# Schematic.net
KiCad netlist of a schematic drawn in Altium Designer
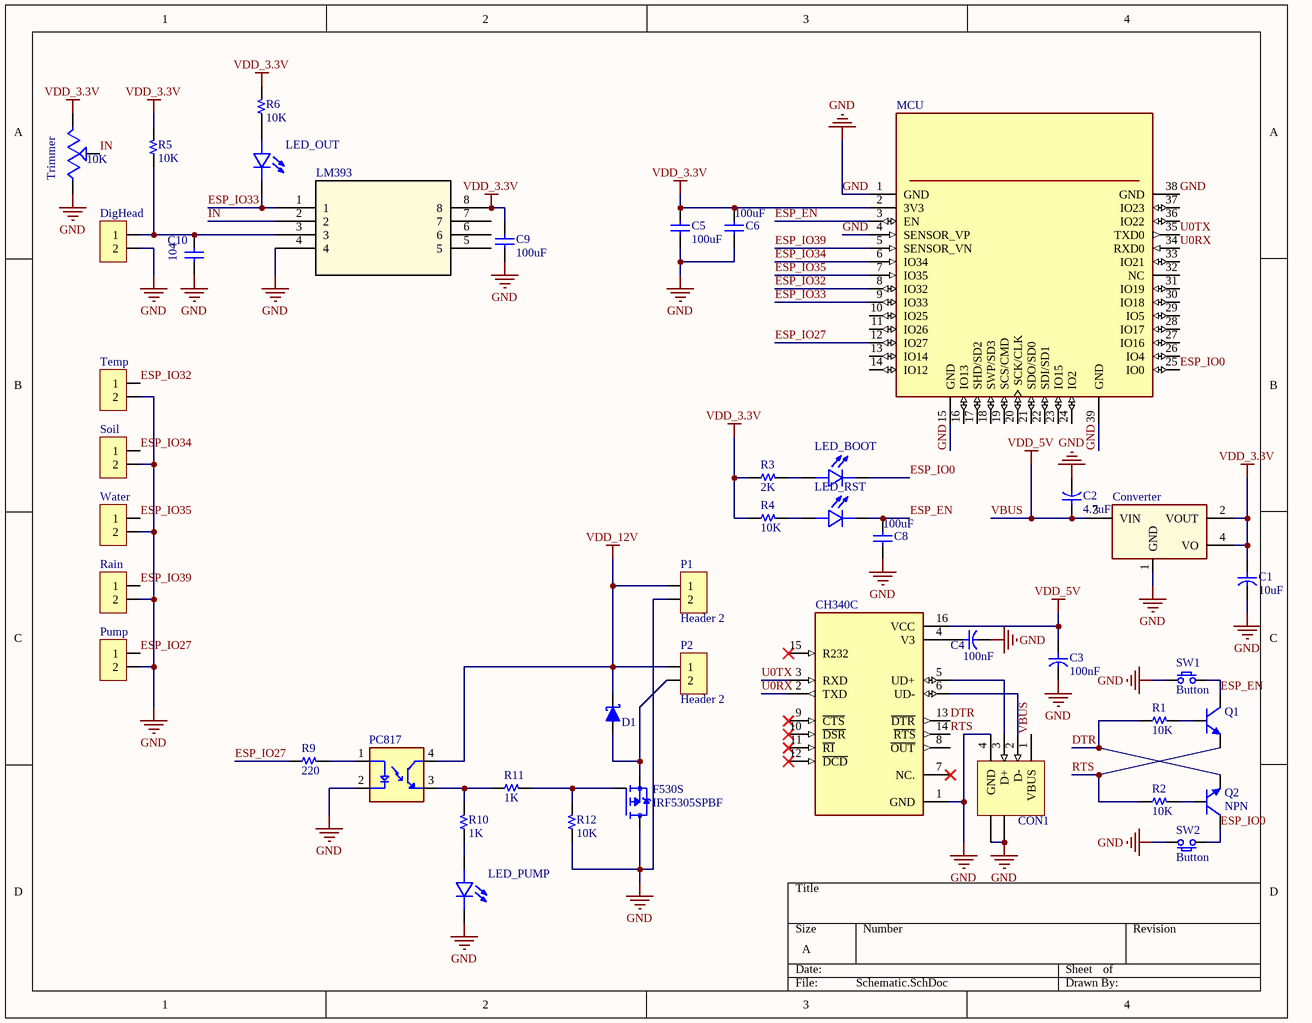
[diagram p0: Schematic.SchDoc]

(export (version "E")
  (design (tool "Eeschema 10.0.6"))
  (components
    (comp (ref "C1")
      (value "10uF")
      (footprint "C SMD TAN 1206 (A)")
      (description "Capacitor pol")
      (libsource (lib "chipfc_libs") (part "Capacitor"))
    )
    (comp (ref "C2")
      (value "4.7uF")
      (footprint "C SMD TAN 1206 (A)")
      (description "Capacitor pol")
      (libsource (lib "chipfc_libs") (part "Capacitor"))
    )
    (comp (ref "C3")
      (value "100nF")
      (footprint "C SMD TAN 1206 (A)")
      (description "Capacitor pol")
      (libsource (lib "chipfc_libs") (part "Capacitor"))
    )
    (comp (ref "C4")
      (value "100nF")
      (footprint "C SMD TAN 1206 (A)")
      (description "Capacitor pol")
      (libsource (lib "chipfc_libs") (part "Capacitor"))
    )
    (comp (ref "C5")
      (value "100uF")
      (footprint "C 0805")
      (description "Capacitor non-pol")
      (libsource (lib "chipfc_libs") (part "Capacitor NP"))
    )
    (comp (ref "C6")
      (value "100uF")
      (footprint "C 0805")
      (description "Capacitor non-pol")
      (libsource (lib "chipfc_libs") (part "Capacitor NP"))
    )
    (comp (ref "C8")
      (value "100uF")
      (footprint "C 0805")
      (description "Capacitor non-pol")
      (libsource (lib "chipfc_libs") (part "Capacitor NP"))
    )
    (comp (ref "C9")
      (value "100uF")
      (footprint "C 0805")
      (description "Capacitor non-pol")
      (libsource (lib "chipfc_libs") (part "Capacitor NP"))
    )
    (comp (ref "C10")
      (value "104")
      (footprint "C 0805")
      (description "Capacitor non-pol")
      (libsource (lib "chipfc_libs") (part "Capacitor NP"))
    )
    (comp (ref "CH340C")
      (value "USB to UART")
      (footprint "SOIC127P600X180-16N")
      (description "USB to serial chip CH340")
      (fields (field (name "MP") "CH340C") (field (name "MF") "WCH"))
      (libsource (lib "CH340C") (part "CH340C"))
    )
    (comp (ref "CON1")
      (value "USB Type A")
      (footprint "CONN/USB/A/FEMALE/RA")
      (description "USB type A, 4 pins")
      (libsource (lib "connectors") (part "CON USB Type A"))
    )
    (comp (ref "Converter")
      (value "1117-3.3")
      (footprint "SOT-223")
      (description "1A LDO Voltage Regulator, ADJ or fixed 1.5/1.8/2.5/2.85/3.3/5V")
      (libsource (lib "chipfc_libs") (part "AMS1117"))
    )
    (comp (ref "D1")
      (value "Diode Schottky")
      (footprint "DO-41")
      (description "Schottky Diode")
      (libsource (lib "chipfc_libs") (part "Diode Schottky"))
    )
    (comp (ref "DigHead")
      (value "Header 2")
      (footprint "HDR/Header/2/2mm")
      (description "Header, 2-Pin")
      (libsource (lib "") (part "Header 2_1"))
    )
    (comp (ref "F530S")
      (value "IRF5305SPBF")
      (footprint "TO254P1524X483-4N")
      (fields (field (name "MF") "Infineon Technologies"))
      (libsource (lib "IRF5305SPBF") (part "IRF5305SPBF"))
    )
    (comp (ref "LED_BOOT")
      (value "VLMS1300-GS08")
      (footprint "LED_VLMS1300-GS08")
      (libsource (lib "VLMS1300-GS08") (part "VLMS1300-GS08"))
    )
    (comp (ref "LED_OUT")
      (value "VLMS1300-GS08")
      (footprint "LED_VLMS1300-GS08")
      (libsource (lib "VLMS1300-GS08") (part "VLMS1300-GS08"))
    )
    (comp (ref "LED_PUMP")
      (value "VLMS1300-GS08")
      (footprint "LED_VLMS1300-GS08")
      (libsource (lib "VLMS1300-GS08") (part "VLMS1300-GS08"))
    )
    (comp (ref "LED_RST")
      (value "VLMS1300-GS08")
      (footprint "LED_VLMS1300-GS08")
      (libsource (lib "VLMS1300-GS08") (part "VLMS1300-GS08"))
    )
    (comp (ref "LM393")
      (value "Comparator")
      (footprint "DIP8_300")
      (description "Description")
      (fields
        (field (name "MANUFACTURER_PART_NUMBER") "LM393")
        (field (name "COPYRIGHT") "Copyright (C) 2025 Ultra Librarian. All rights reserved.")
      )
      (libsource (lib "LM393") (part "LM393"))
    )
    (comp (ref "MCU")
      (value "ESP32-WROOM-32")
      (footprint "MODULE_ESP32-WROOM-32")
      (fields (field (name "MF") "Espressif Systems") (field (name "MP") "ESP32-WROOM-32D"))
      (libsource (lib "ESP32") (part "ESP32-WROOM-32"))
    )
    (comp (ref "P1")
      (value "Header 2")
      (footprint "HDR/Terminal/2")
      (description "Header, 2-Pin")
      (libsource (lib "connectors") (part "Header 2"))
    )
    (comp (ref "P2")
      (value "Header 2")
      (footprint "HDR/Terminal/2")
      (description "Header, 2-Pin")
      (libsource (lib "connectors") (part "Header 2"))
    )
    (comp (ref "PC817")
      (value "PC817X2NIP1B")
      (footprint "SOIC254P960X420-4N")
      (description "Optocoupler DC-IN 1-CH Transistor DC-OUT 4-Pin DIP SMD T/R")
      (fields (field (name "MF") "Sharp Microelectronics"))
      (libsource (lib "PC817X2NIP1B") (part "PC817X2NIP1B"))
    )
    (comp (ref "Pump")
      (value "Header 2")
      (footprint "HDR/Header/2/2mm")
      (description "Header, 2-Pin")
      (libsource (lib "") (part "Header 2_1"))
    )
    (comp (ref "Q1")
      (value "NPN")
      (footprint "SOT-23")
      (description "NPN Bipolar Transistor")
      (libsource (lib "chipfc_libs") (part "Transistor NPN"))
    )
    (comp (ref "Q2")
      (value "NPN")
      (footprint "SOT-23")
      (description "NPN Bipolar Transistor")
      (libsource (lib "chipfc_libs") (part "Transistor NPN"))
    )
    (comp (ref "R1")
      (value "10K")
      (footprint "R 0402")
      (description "Resistor")
      (libsource (lib "chipfc_libs") (part "Resistor"))
    )
    (comp (ref "R2")
      (value "10K")
      (footprint "R 0402")
      (description "Resistor")
      (libsource (lib "chipfc_libs") (part "Resistor"))
    )
    (comp (ref "R3")
      (value "2K")
      (footprint "R 0402")
      (description "Resistor")
      (libsource (lib "chipfc_libs") (part "Resistor"))
    )
    (comp (ref "R4")
      (value "10K")
      (footprint "R 0402")
      (description "Resistor")
      (libsource (lib "chipfc_libs") (part "Resistor"))
    )
    (comp (ref "R5")
      (value "10K")
      (footprint "R 0402")
      (description "Resistor")
      (libsource (lib "chipfc_libs") (part "Resistor"))
    )
    (comp (ref "R6")
      (value "10K")
      (footprint "R 0402")
      (description "Resistor")
      (libsource (lib "chipfc_libs") (part "Resistor"))
    )
    (comp (ref "R9")
      (value "220")
      (footprint "R 0402")
      (description "Resistor")
      (libsource (lib "chipfc_libs") (part "Resistor"))
    )
    (comp (ref "R10")
      (value "1K")
      (footprint "R 0402")
      (description "Resistor")
      (libsource (lib "chipfc_libs") (part "Resistor"))
    )
    (comp (ref "R11")
      (value "1K")
      (footprint "R 0402")
      (description "Resistor")
      (libsource (lib "chipfc_libs") (part "Resistor"))
    )
    (comp (ref "R12")
      (value "10K")
      (footprint "R 0402")
      (description "Resistor")
      (libsource (lib "chipfc_libs") (part "Resistor"))
    )
    (comp (ref "Rain")
      (value "Header 2")
      (footprint "HDR/Header/2/2mm")
      (description "Header, 2-Pin")
      (libsource (lib "") (part "Header 2_1"))
    )
    (comp (ref "Soil")
      (value "~")
      (footprint "HDR/Header/2/2mm")
      (description "Header, 2-Pin")
      (libsource (lib "") (part "Header 2_1"))
    )
    (comp (ref "SW1")
      (value "Button")
      (footprint "SW/2/DIP")
      (description "Tact switch 2 pin")
      (libsource (lib "chipfc_libs") (part "SW SPST"))
    )
    (comp (ref "SW2")
      (value "Button")
      (footprint "SW/2/DIP")
      (description "Tact switch 2 pin")
      (libsource (lib "chipfc_libs") (part "SW SPST"))
    )
    (comp (ref "Temp")
      (value "Temp Sensor")
      (footprint "HDR/Header/2/2mm")
      (description "Header, 2-Pin")
      (libsource (lib "") (part "Header 2_1"))
    )
    (comp (ref "Trimmer")
      (value "10K")
      (footprint "TRIM_3386F-1-103T")
      (fields (field (name "MF") "Bourns") (field (name "MP") "3386F-1-103"))
      (libsource (lib "3386F-1-103T") (part "3386F-1-103T"))
    )
    (comp (ref "Water")
      (value "Header 2")
      (footprint "HDR/Header/2/2mm")
      (description "Header, 2-Pin")
      (libsource (lib "") (part "Header 2_1"))
    )
  )
  (nets
    (net (code "1") (name "/DTR") (class "Default")
      (node (ref "CH340C") (pin "13") (pinfunction "~{DTR}_13") (pintype "output"))
      (node (ref "Q2") (pin "2") (pinfunction "E_2") (pintype "passive"))
      (node (ref "R1") (pin "1") (pinfunction "1_1") (pintype "passive"))
    )
    (net (code "2") (name "/ESP_EN") (class "Default")
      (node (ref "C8") (pin "1") (pinfunction "1_1") (pintype "passive"))
      (node (ref "LED_RST") (pin "C") (pinfunction "C_C") (pintype "passive"))
      (node (ref "MCU") (pin "3") (pinfunction "EN_3") (pintype "bidirectional"))
      (node (ref "Q1") (pin "3") (pinfunction "C_3") (pintype "passive"))
      (node (ref "SW1") (pin "2") (pinfunction "2_2") (pintype "passive"))
    )
    (net (code "3") (name "/ESP_IO0") (class "Default")
      (node (ref "LED_BOOT") (pin "C") (pinfunction "C_C") (pintype "passive"))
      (node (ref "MCU") (pin "25") (pinfunction "IO0_25") (pintype "bidirectional"))
      (node (ref "Q2") (pin "3") (pinfunction "C_3") (pintype "passive"))
      (node (ref "SW2") (pin "1") (pinfunction "1_1") (pintype "passive"))
    )
    (net (code "4") (name "/ESP_IO27") (class "Default")
      (node (ref "MCU") (pin "12") (pinfunction "IO27_12") (pintype "bidirectional"))
      (node (ref "Pump") (pin "1") (pinfunction "1_1") (pintype "passive"))
      (node (ref "R9") (pin "1") (pinfunction "1_1") (pintype "passive"))
    )
    (net (code "5") (name "/ESP_IO32") (class "Default")
      (node (ref "MCU") (pin "8") (pinfunction "IO32_8") (pintype "bidirectional"))
      (node (ref "Temp") (pin "1") (pinfunction "1_1") (pintype "passive"))
    )
    (net (code "6") (name "/ESP_IO33") (class "Default")
      (node (ref "LED_OUT") (pin "C") (pinfunction "C_C") (pintype "passive"))
      (node (ref "LM393") (pin "1") (pinfunction "1_1") (pintype "passive"))
      (node (ref "MCU") (pin "9") (pinfunction "IO33_9") (pintype "bidirectional"))
    )
    (net (code "7") (name "/ESP_IO34") (class "Default")
      (node (ref "MCU") (pin "6") (pinfunction "IO34_6") (pintype "input"))
      (node (ref "Soil") (pin "1") (pinfunction "1_1") (pintype "passive"))
    )
    (net (code "8") (name "/ESP_IO35") (class "Default")
      (node (ref "MCU") (pin "7") (pinfunction "IO35_7") (pintype "input"))
      (node (ref "Water") (pin "1") (pinfunction "1_1") (pintype "passive"))
    )
    (net (code "9") (name "/ESP_IO39") (class "Default")
      (node (ref "MCU") (pin "5") (pinfunction "SENSOR_VN_5") (pintype "input"))
      (node (ref "Rain") (pin "1") (pinfunction "1_1") (pintype "passive"))
    )
    (net (code "10") (name "/IN") (class "Default")
      (node (ref "LM393") (pin "2") (pinfunction "2_2") (pintype "passive"))
      (node (ref "Trimmer") (pin "2") (pinfunction "WIPER_2") (pintype "passive"))
    )
    (net (code "11") (name "/RTS") (class "Default")
      (node (ref "CH340C") (pin "14") (pinfunction "~{RTS}_14") (pintype "output"))
      (node (ref "Q1") (pin "2") (pinfunction "E_2") (pintype "passive"))
      (node (ref "R2") (pin "1") (pinfunction "1_1") (pintype "passive"))
    )
    (net (code "12") (name "/U0RX") (class "Default")
      (node (ref "CH340C") (pin "2") (pinfunction "TXD_2") (pintype "output"))
      (node (ref "MCU") (pin "34") (pinfunction "RXD0_34") (pintype "input"))
    )
    (net (code "13") (name "/U0TX") (class "Default")
      (node (ref "CH340C") (pin "3") (pinfunction "RXD_3") (pintype "input"))
      (node (ref "MCU") (pin "35") (pinfunction "TXD0_35") (pintype "output"))
    )
    (net (code "14") (name "GND") (class "Default")
      (node (ref "C1") (pin "2") (pinfunction "2_2") (pintype "passive"))
      (node (ref "C10") (pin "2") (pinfunction "2_2") (pintype "passive"))
      (node (ref "C2") (pin "2") (pinfunction "2_2") (pintype "passive"))
      (node (ref "C3") (pin "2") (pinfunction "2_2") (pintype "passive"))
      (node (ref "C4") (pin "2") (pinfunction "2_2") (pintype "passive"))
      (node (ref "C5") (pin "2") (pinfunction "2_2") (pintype "passive"))
      (node (ref "C6") (pin "2") (pinfunction "2_2") (pintype "passive"))
      (node (ref "C8") (pin "2") (pinfunction "2_2") (pintype "passive"))
      (node (ref "C9") (pin "2") (pinfunction "2_2") (pintype "passive"))
      (node (ref "CH340C") (pin "1") (pinfunction "GND_1") (pintype "power_in"))
      (node (ref "CON1") (pin "4") (pinfunction "GND_4") (pintype "power_in"))
      (node (ref "CON1") (pin "5") (pinfunction "SHLD_5") (pintype "passive"))
      (node (ref "CON1") (pin "6") (pinfunction "SHLD_6") (pintype "passive"))
      (node (ref "Converter") (pin "1") (pinfunction "GND_1") (pintype "passive"))
      (node (ref "DigHead") (pin "2") (pinfunction "2_2") (pintype "passive"))
      (node (ref "F530S") (pin "4") (pinfunction "D_4") (pintype "passive"))
      (node (ref "LED_PUMP") (pin "C") (pinfunction "C_C") (pintype "passive"))
      (node (ref "LM393") (pin "4") (pinfunction "4_4") (pintype "passive"))
      (node (ref "MCU") (pin "1") (pinfunction "GND_1") (pintype "power_in"))
      (node (ref "MCU") (pin "15") (pinfunction "GND_15") (pintype "power_in"))
      (node (ref "MCU") (pin "38") (pinfunction "GND_38") (pintype "power_in"))
      (node (ref "MCU") (pin "39") (pinfunction "GND_39") (pintype "power_in"))
      (node (ref "MCU") (pin "4") (pinfunction "SENSOR_VP_4") (pintype "input"))
      (node (ref "P1") (pin "2") (pinfunction "2_2") (pintype "passive"))
      (node (ref "PC817") (pin "2") (pinfunction "C_2") (pintype "passive"))
      (node (ref "Pump") (pin "2") (pinfunction "2_2") (pintype "passive"))
      (node (ref "R12") (pin "1") (pinfunction "1_1") (pintype "passive"))
      (node (ref "Rain") (pin "2") (pinfunction "2_2") (pintype "passive"))
      (node (ref "SW1") (pin "1") (pinfunction "1_1") (pintype "passive"))
      (node (ref "SW2") (pin "2") (pinfunction "2_2") (pintype "passive"))
      (node (ref "Soil") (pin "2") (pinfunction "2_2") (pintype "passive"))
      (node (ref "Temp") (pin "2") (pinfunction "2_2") (pintype "passive"))
      (node (ref "Trimmer") (pin "1") (pinfunction "CCW_1") (pintype "passive"))
      (node (ref "Water") (pin "2") (pinfunction "2_2") (pintype "passive"))
    )
    (net (code "15") (name "Net-(C10-Pad1)") (class "Default")
      (node (ref "C10") (pin "1") (pinfunction "1_1") (pintype "passive"))
      (node (ref "DigHead") (pin "1") (pinfunction "1_1") (pintype "passive"))
      (node (ref "LM393") (pin "3") (pinfunction "3_3") (pintype "passive"))
      (node (ref "R5") (pin "1") (pinfunction "1_1") (pintype "passive"))
    )
    (net (code "16") (name "Net-(CH340C-UD+)") (class "Default")
      (node (ref "CH340C") (pin "5") (pinfunction "UD+_5") (pintype "bidirectional"))
      (node (ref "CON1") (pin "3") (pinfunction "D+_3") (pintype "input"))
    )
    (net (code "17") (name "Net-(CH340C-UD-)") (class "Default")
      (node (ref "CH340C") (pin "6") (pinfunction "UD-_6") (pintype "bidirectional"))
      (node (ref "CON1") (pin "2") (pinfunction "D-_2") (pintype "input"))
    )
    (net (code "18") (name "Net-(CH340C-V3)") (class "Default")
      (node (ref "C4") (pin "1") (pinfunction "1_1") (pintype "passive"))
      (node (ref "CH340C") (pin "4") (pinfunction "V3_4") (pintype "power_in"))
    )
    (net (code "19") (name "Net-(D1-A)") (class "Default")
      (node (ref "D1") (pin "1") (pinfunction "A_1") (pintype "passive"))
      (node (ref "F530S") (pin "3") (pinfunction "S_3") (pintype "passive"))
      (node (ref "P2") (pin "2") (pinfunction "2_2") (pintype "passive"))
    )
    (net (code "20") (name "Net-(F530S-G)") (class "Default")
      (node (ref "F530S") (pin "1") (pinfunction "G_1") (pintype "passive"))
      (node (ref "R11") (pin "2") (pinfunction "2_2") (pintype "passive"))
      (node (ref "R12") (pin "2") (pinfunction "2_2") (pintype "passive"))
    )
    (net (code "21") (name "Net-(LED_BOOT-PadA)") (class "Default")
      (node (ref "LED_BOOT") (pin "A") (pinfunction "A_A") (pintype "passive"))
      (node (ref "R3") (pin "2") (pinfunction "2_2") (pintype "passive"))
    )
    (net (code "22") (name "Net-(LED_OUT-PadA)") (class "Default")
      (node (ref "LED_OUT") (pin "A") (pinfunction "A_A") (pintype "passive"))
      (node (ref "R6") (pin "1") (pinfunction "1_1") (pintype "passive"))
    )
    (net (code "23") (name "Net-(LED_PUMP-PadA)") (class "Default")
      (node (ref "LED_PUMP") (pin "A") (pinfunction "A_A") (pintype "passive"))
      (node (ref "R10") (pin "1") (pinfunction "1_1") (pintype "passive"))
    )
    (net (code "24") (name "Net-(LED_RST-PadA)") (class "Default")
      (node (ref "LED_RST") (pin "A") (pinfunction "A_A") (pintype "passive"))
      (node (ref "R4") (pin "2") (pinfunction "2_2") (pintype "passive"))
    )
    (net (code "25") (name "Net-(PC817-A)") (class "Default")
      (node (ref "PC817") (pin "1") (pinfunction "A_1") (pintype "passive"))
      (node (ref "R9") (pin "2") (pinfunction "2_2") (pintype "passive"))
    )
    (net (code "26") (name "Net-(PC817-ET)") (class "Default")
      (node (ref "PC817") (pin "3") (pinfunction "ET_3") (pintype "passive"))
      (node (ref "R10") (pin "2") (pinfunction "2_2") (pintype "passive"))
      (node (ref "R11") (pin "1") (pinfunction "1_1") (pintype "passive"))
    )
    (net (code "27") (name "Net-(Q1-B)") (class "Default")
      (node (ref "Q1") (pin "1") (pinfunction "B_1") (pintype "passive"))
      (node (ref "R1") (pin "2") (pinfunction "2_2") (pintype "passive"))
    )
    (net (code "28") (name "Net-(Q2-B)") (class "Default")
      (node (ref "Q2") (pin "1") (pinfunction "B_1") (pintype "passive"))
      (node (ref "R2") (pin "2") (pinfunction "2_2") (pintype "passive"))
    )
    (net (code "29") (name "VDD_3.3V") (class "Default")
      (node (ref "C1") (pin "1") (pinfunction "1_1") (pintype "passive"))
      (node (ref "C5") (pin "1") (pinfunction "1_1") (pintype "passive"))
      (node (ref "C6") (pin "1") (pinfunction "1_1") (pintype "passive"))
      (node (ref "C9") (pin "1") (pinfunction "1_1") (pintype "passive"))
      (node (ref "Converter") (pin "2") (pinfunction "VOUT_2") (pintype "passive"))
      (node (ref "Converter") (pin "4") (pinfunction "VO_4") (pintype "passive"))
      (node (ref "LM393") (pin "8") (pinfunction "8_8") (pintype "passive"))
      (node (ref "MCU") (pin "2") (pinfunction "3V3_2") (pintype "power_in"))
      (node (ref "R3") (pin "1") (pinfunction "1_1") (pintype "passive"))
      (node (ref "R4") (pin "1") (pinfunction "1_1") (pintype "passive"))
      (node (ref "R5") (pin "2") (pinfunction "2_2") (pintype "passive"))
      (node (ref "R6") (pin "2") (pinfunction "2_2") (pintype "passive"))
      (node (ref "Trimmer") (pin "3") (pinfunction "CW_3") (pintype "passive"))
    )
    (net (code "30") (name "VDD_5V") (class "Default")
      (node (ref "C2") (pin "1") (pinfunction "1_1") (pintype "passive"))
      (node (ref "C3") (pin "1") (pinfunction "1_1") (pintype "passive"))
      (node (ref "CH340C") (pin "16") (pinfunction "VCC_16") (pintype "power_in"))
      (node (ref "CON1") (pin "1") (pinfunction "VBUS_1") (pintype "power_in"))
      (node (ref "Converter") (pin "3") (pinfunction "VIN_3") (pintype "power_in"))
    )
    (net (code "31") (name "VDD_12V") (class "Default")
      (node (ref "D1") (pin "2") (pinfunction "K_2") (pintype "passive"))
      (node (ref "P1") (pin "1") (pinfunction "1_1") (pintype "passive"))
      (node (ref "P2") (pin "1") (pinfunction "1_1") (pintype "passive"))
      (node (ref "PC817") (pin "4") (pinfunction "CT_4") (pintype "passive"))
    )
    (net (code "32") (name "unconnected-(CH340C-NC.-Pad7)") (class "Default")
      (node (ref "CH340C") (pin "7") (pinfunction "NC._7") (pintype "passive+no_connect"))
    )
    (net (code "33") (name "unconnected-(CH340C-R232-Pad15)") (class "Default")
      (node (ref "CH340C") (pin "15") (pinfunction "R232_15") (pintype "input+no_connect"))
    )
    (net (code "34") (name "unconnected-(CH340C-~{CTS}-Pad9)") (class "Default")
      (node (ref "CH340C") (pin "9") (pinfunction "~{CTS}_9") (pintype "input+no_connect"))
    )
    (net (code "35") (name "unconnected-(CH340C-~{DCD}-Pad12)") (class "Default")
      (node (ref "CH340C") (pin "12") (pinfunction "~{DCD}_12") (pintype "input+no_connect"))
    )
    (net (code "36") (name "unconnected-(CH340C-~{DSR}-Pad10)") (class "Default")
      (node (ref "CH340C") (pin "10") (pinfunction "~{DSR}_10") (pintype "input+no_connect"))
    )
    (net (code "37") (name "unconnected-(CH340C-~{OUT}-Pad8)") (class "Default")
      (node (ref "CH340C") (pin "8") (pinfunction "~{OUT}_8") (pintype "output"))
    )
    (net (code "38") (name "unconnected-(CH340C-~{RI}-Pad11)") (class "Default")
      (node (ref "CH340C") (pin "11") (pinfunction "~{RI}_11") (pintype "input+no_connect"))
    )
    (net (code "39") (name "unconnected-(LM393-Pad5)") (class "Default")
      (node (ref "LM393") (pin "5") (pinfunction "5_5") (pintype "passive"))
    )
    (net (code "40") (name "unconnected-(LM393-Pad6)") (class "Default")
      (node (ref "LM393") (pin "6") (pinfunction "6_6") (pintype "passive"))
    )
    (net (code "41") (name "unconnected-(LM393-Pad7)") (class "Default")
      (node (ref "LM393") (pin "7") (pinfunction "7_7") (pintype "passive"))
    )
    (net (code "42") (name "unconnected-(MCU-IO2-Pad24)") (class "Default")
      (node (ref "MCU") (pin "24") (pinfunction "IO2_24") (pintype "bidirectional"))
    )
    (net (code "43") (name "unconnected-(MCU-IO4-Pad26)") (class "Default")
      (node (ref "MCU") (pin "26") (pinfunction "IO4_26") (pintype "bidirectional"))
    )
    (net (code "44") (name "unconnected-(MCU-IO5-Pad29)") (class "Default")
      (node (ref "MCU") (pin "29") (pinfunction "IO5_29") (pintype "bidirectional"))
    )
    (net (code "45") (name "unconnected-(MCU-IO12-Pad14)") (class "Default")
      (node (ref "MCU") (pin "14") (pinfunction "IO12_14") (pintype "bidirectional"))
    )
    (net (code "46") (name "unconnected-(MCU-IO13-Pad16)") (class "Default")
      (node (ref "MCU") (pin "16") (pinfunction "IO13_16") (pintype "bidirectional"))
    )
    (net (code "47") (name "unconnected-(MCU-IO14-Pad13)") (class "Default")
      (node (ref "MCU") (pin "13") (pinfunction "IO14_13") (pintype "bidirectional"))
    )
    (net (code "48") (name "unconnected-(MCU-IO15-Pad23)") (class "Default")
      (node (ref "MCU") (pin "23") (pinfunction "IO15_23") (pintype "bidirectional"))
    )
    (net (code "49") (name "unconnected-(MCU-IO16-Pad27)") (class "Default")
      (node (ref "MCU") (pin "27") (pinfunction "IO16_27") (pintype "bidirectional"))
    )
    (net (code "50") (name "unconnected-(MCU-IO17-Pad28)") (class "Default")
      (node (ref "MCU") (pin "28") (pinfunction "IO17_28") (pintype "bidirectional"))
    )
    (net (code "51") (name "unconnected-(MCU-IO18-Pad30)") (class "Default")
      (node (ref "MCU") (pin "30") (pinfunction "IO18_30") (pintype "bidirectional"))
    )
    (net (code "52") (name "unconnected-(MCU-IO19-Pad31)") (class "Default")
      (node (ref "MCU") (pin "31") (pinfunction "IO19_31") (pintype "bidirectional"))
    )
    (net (code "53") (name "unconnected-(MCU-IO21-Pad33)") (class "Default")
      (node (ref "MCU") (pin "33") (pinfunction "IO21_33") (pintype "bidirectional"))
    )
    (net (code "54") (name "unconnected-(MCU-IO22-Pad36)") (class "Default")
      (node (ref "MCU") (pin "36") (pinfunction "IO22_36") (pintype "bidirectional"))
    )
    (net (code "55") (name "unconnected-(MCU-IO23-Pad37)") (class "Default")
      (node (ref "MCU") (pin "37") (pinfunction "IO23_37") (pintype "bidirectional"))
    )
    (net (code "56") (name "unconnected-(MCU-IO25-Pad10)") (class "Default")
      (node (ref "MCU") (pin "10") (pinfunction "IO25_10") (pintype "bidirectional"))
    )
    (net (code "57") (name "unconnected-(MCU-IO26-Pad11)") (class "Default")
      (node (ref "MCU") (pin "11") (pinfunction "IO26_11") (pintype "bidirectional"))
    )
    (net (code "58") (name "unconnected-(MCU-NC-Pad32)") (class "Default")
      (node (ref "MCU") (pin "32") (pinfunction "NC_32") (pintype "power_in"))
    )
    (net (code "59") (name "unconnected-(MCU-SCK{slash}CLK-Pad20)") (class "Default")
      (node (ref "MCU") (pin "20") (pinfunction "SCK/CLK_20") (pintype "bidirectional"))
    )
    (net (code "60") (name "unconnected-(MCU-SCS{slash}CMD-Pad19)") (class "Default")
      (node (ref "MCU") (pin "19") (pinfunction "SCS/CMD_19") (pintype "bidirectional"))
    )
    (net (code "61") (name "unconnected-(MCU-SDI{slash}SD1-Pad22)") (class "Default")
      (node (ref "MCU") (pin "22") (pinfunction "SDI/SD1_22") (pintype "bidirectional"))
    )
    (net (code "62") (name "unconnected-(MCU-SDO{slash}SD0-Pad21)") (class "Default")
      (node (ref "MCU") (pin "21") (pinfunction "SDO/SD0_21") (pintype "bidirectional"))
    )
    (net (code "63") (name "unconnected-(MCU-SHD{slash}SD2-Pad17)") (class "Default")
      (node (ref "MCU") (pin "17") (pinfunction "SHD/SD2_17") (pintype "bidirectional"))
    )
    (net (code "64") (name "unconnected-(MCU-SWP{slash}SD3-Pad18)") (class "Default")
      (node (ref "MCU") (pin "18") (pinfunction "SWP/SD3_18") (pintype "bidirectional"))
    )
  )
)
